# t10_programmin_adapter.net
KiCad netlist of a schematic drawn in EAGLE
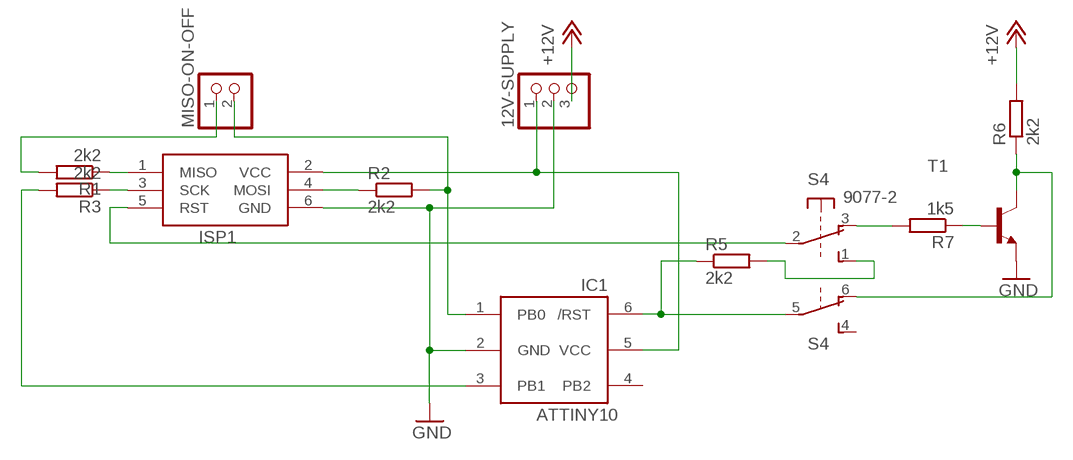
[diagram p0: schematic, sheet 1]

(export (version "E")
  (design (tool "Eeschema 10.0.6"))
  (components
    (comp (ref "12V-SUPPLY")
      (value "PINHD-1X3/90")
      (footprint "eagle-import:1X03_90")
      (libsource (lib "eagle-import") (part "PINHD-1X3/90"))
    )
    (comp (ref "IC1")
      (value "ATTINY10")
      (footprint "eagle-import:SOT23-6")
      (libsource (lib "eagle-import") (part "ATTINY10"))
    )
    (comp (ref "ISP1")
      (value "AVRISP-6")
      (footprint "eagle-import:AVRISP")
      (libsource (lib "eagle-import") (part "AVRISP-6"))
    )
    (comp (ref "MISO-ON-OFF")
      (value "PINHD-1X2")
      (footprint "eagle-import:1X02")
      (libsource (lib "eagle-import") (part "PINHD-1X2"))
    )
    (comp (ref "R1")
      (value "2k2")
      (footprint "eagle-import:0204_7")
      (libsource (lib "eagle-import") (part "R-EU_0204/7"))
    )
    (comp (ref "R2")
      (value "2k2")
      (footprint "eagle-import:0204_7")
      (libsource (lib "eagle-import") (part "R-EU_0204/7"))
    )
    (comp (ref "R3")
      (value "2k2")
      (footprint "eagle-import:0204_7")
      (libsource (lib "eagle-import") (part "R-EU_0204/7"))
    )
    (comp (ref "R5")
      (value "2k2")
      (footprint "eagle-import:0204_7")
      (libsource (lib "eagle-import") (part "R-EU_0204/7"))
    )
    (comp (ref "R6")
      (value "2k2")
      (footprint "eagle-import:0204_7")
      (libsource (lib "eagle-import") (part "R-EU_0204/7"))
    )
    (comp (ref "R7")
      (value "1k5")
      (footprint "eagle-import:0207_2V")
      (libsource (lib "eagle-import") (part "R-EU_0207/2V"))
    )
    (comp (ref "S4")
      (value "9077-2")
      (footprint "eagle-import:9077-2")
      (libsource (lib "eagle-import") (part "9077-2"))
    )
    (comp (ref "T1")
      (value "2N6517-NPN-TO92-CBE")
      (footprint "eagle-import:TO92-CBE")
      (libsource (lib "eagle-import") (part "-NPN-TO92-CBE2N6517"))
    )
  )
  (nets
    (net (code "1") (name "+12V") (class "Default")
      (node (ref "12V-SUPPLY") (pin "3") (pinfunction "3_3") (pintype "passive"))
      (node (ref "R6") (pin "2") (pinfunction "2_2") (pintype "passive"))
    )
    (net (code "2") (name "GND") (class "Default")
      (node (ref "12V-SUPPLY") (pin "2") (pinfunction "2_2") (pintype "passive"))
      (node (ref "IC1") (pin "2") (pinfunction "GND_2") (pintype "power_in"))
      (node (ref "ISP1") (pin "6") (pinfunction "GND_6") (pintype "power_in"))
      (node (ref "T1") (pin "E") (pinfunction "E_E") (pintype "passive"))
    )
    (net (code "3") (name "Net-(IC1-PB0)") (class "Default")
      (node (ref "IC1") (pin "1") (pinfunction "PB0_1") (pintype "bidirectional"))
      (node (ref "MISO-ON-OFF") (pin "2") (pinfunction "2_2") (pintype "passive"))
      (node (ref "R2") (pin "2") (pinfunction "2_2") (pintype "passive"))
    )
    (net (code "4") (name "Net-(IC1-PB1)") (class "Default")
      (node (ref "IC1") (pin "3") (pinfunction "PB1_3") (pintype "bidirectional"))
      (node (ref "R3") (pin "2") (pinfunction "2_2") (pintype "passive"))
    )
    (net (code "5") (name "Net-(IC1-VCC)") (class "Default")
      (node (ref "12V-SUPPLY") (pin "1") (pinfunction "1_1") (pintype "passive"))
      (node (ref "IC1") (pin "5") (pinfunction "VCC_5") (pintype "power_in"))
      (node (ref "ISP1") (pin "2") (pinfunction "VCC_2") (pintype "power_in"))
    )
    (net (code "6") (name "Net-(IC1-{slash}RST)") (class "Default")
      (node (ref "IC1") (pin "6") (pinfunction "/RST_6") (pintype "bidirectional"))
      (node (ref "R5") (pin "1") (pinfunction "1_1") (pintype "passive"))
      (node (ref "S4") (pin "5") (pinfunction "P_5") (pintype "passive"))
    )
    (net (code "7") (name "Net-(ISP1-MISO)") (class "Default")
      (node (ref "ISP1") (pin "1") (pinfunction "MISO_1") (pintype "input"))
      (node (ref "R1") (pin "1") (pinfunction "1_1") (pintype "passive"))
    )
    (net (code "8") (name "Net-(ISP1-MOSI)") (class "Default")
      (node (ref "ISP1") (pin "4") (pinfunction "MOSI_4") (pintype "output"))
      (node (ref "R2") (pin "1") (pinfunction "1_1") (pintype "passive"))
    )
    (net (code "9") (name "Net-(ISP1-RST)") (class "Default")
      (node (ref "ISP1") (pin "5") (pinfunction "RST_5") (pintype "output"))
      (node (ref "S4") (pin "2") (pinfunction "P_2") (pintype "passive"))
    )
    (net (code "10") (name "Net-(ISP1-SCK)") (class "Default")
      (node (ref "ISP1") (pin "3") (pinfunction "SCK_3") (pintype "output"))
      (node (ref "R3") (pin "1") (pinfunction "1_1") (pintype "passive"))
    )
    (net (code "11") (name "Net-(MISO-ON-OFF-Pad1)") (class "Default")
      (node (ref "MISO-ON-OFF") (pin "1") (pinfunction "1_1") (pintype "passive"))
      (node (ref "R1") (pin "2") (pinfunction "2_2") (pintype "passive"))
    )
    (net (code "12") (name "Net-(R7-Pad1)") (class "Default")
      (node (ref "R7") (pin "1") (pinfunction "1_1") (pintype "passive"))
      (node (ref "T1") (pin "B") (pinfunction "B_B") (pintype "passive"))
    )
    (net (code "13") (name "Net-(S4A-O)") (class "Default")
      (node (ref "R7") (pin "2") (pinfunction "2_2") (pintype "passive"))
      (node (ref "S4") (pin "3") (pinfunction "O_3") (pintype "passive"))
    )
    (net (code "14") (name "Net-(S4A-S)") (class "Default")
      (node (ref "R5") (pin "2") (pinfunction "2_2") (pintype "passive"))
      (node (ref "S4") (pin "1") (pinfunction "S_1") (pintype "passive"))
    )
    (net (code "15") (name "Net-(S4B-O)") (class "Default")
      (node (ref "R6") (pin "1") (pinfunction "1_1") (pintype "passive"))
      (node (ref "S4") (pin "6") (pinfunction "O_6") (pintype "passive"))
      (node (ref "T1") (pin "C") (pinfunction "C_C") (pintype "passive"))
    )
    (net (code "16") (name "unconnected-(IC1-PB2-Pad4)") (class "Default")
      (node (ref "IC1") (pin "4") (pinfunction "PB2_4") (pintype "bidirectional"))
    )
    (net (code "17") (name "unconnected-(S4B-S-Pad4)") (class "Default")
      (node (ref "S4") (pin "4") (pinfunction "S_4") (pintype "passive"))
    )
  )
)
